# STM32G473RET6_PINOUT.net
KiCad netlist of a schematic drawn in Altium Designer
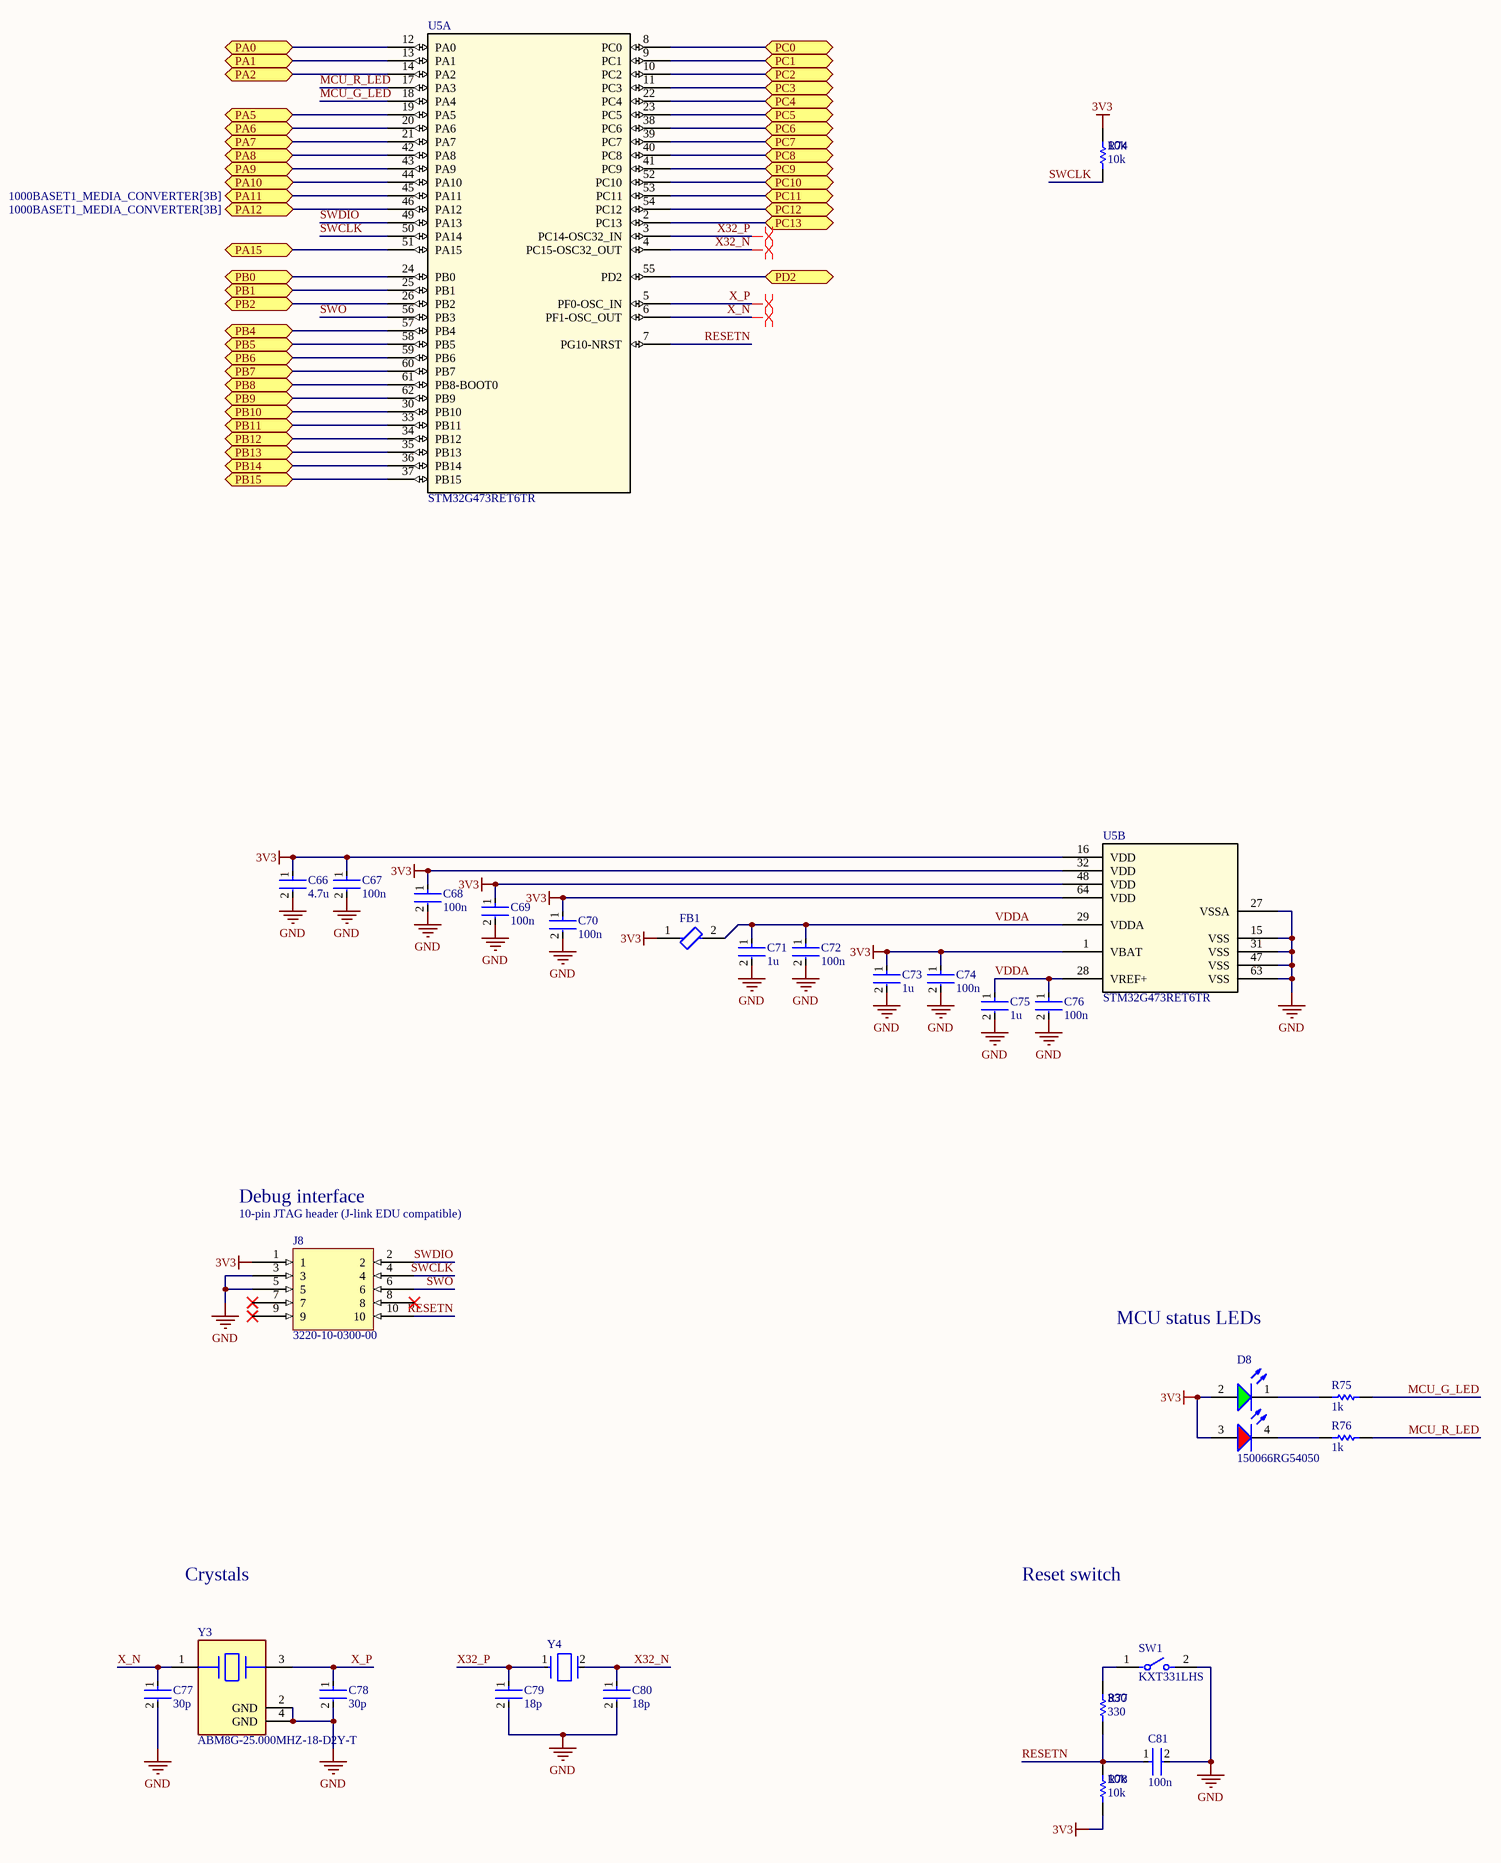
[diagram p0: STM32G473RET6_PINOUT.SchDoc]

(export (version "E")
  (design (tool "Eeschema 10.0.6"))
  (components
    (comp (ref "C66")
      (value "4.7u")
      (footprint "FP-0402-L_1_0_0_05-W_0_5-IPC_A")
      (description "LARGE PADS, 0402 CAP, CHANGE COMMENT TO MATCH REAL P/N")
      (libsource (lib "Space Concordia") (part "b4654b650e69147ec39a6b967a45e02"))
    )
    (comp (ref "C67")
      (value "100n")
      (footprint "FP-0402-L_1_0_0_05-W_0_5-IPC_A")
      (description "LARGE PADS, 0402 CAP, CHANGE COMMENT TO MATCH REAL P/N")
      (libsource (lib "Space Concordia") (part "b4654b650e69147ec39a6b967a45e02"))
    )
    (comp (ref "C68")
      (value "100n")
      (footprint "FP-0402-L_1_0_0_05-W_0_5-IPC_A")
      (description "LARGE PADS, 0402 CAP, CHANGE COMMENT TO MATCH REAL P/N")
      (libsource (lib "Space Concordia") (part "b4654b650e69147ec39a6b967a45e02"))
    )
    (comp (ref "C69")
      (value "100n")
      (footprint "FP-0402-L_1_0_0_05-W_0_5-IPC_A")
      (description "LARGE PADS, 0402 CAP, CHANGE COMMENT TO MATCH REAL P/N")
      (libsource (lib "Space Concordia") (part "b4654b650e69147ec39a6b967a45e02"))
    )
    (comp (ref "C70")
      (value "100n")
      (footprint "FP-0402-L_1_0_0_05-W_0_5-IPC_A")
      (description "LARGE PADS, 0402 CAP, CHANGE COMMENT TO MATCH REAL P/N")
      (libsource (lib "Space Concordia") (part "b4654b650e69147ec39a6b967a45e02"))
    )
    (comp (ref "C71")
      (value "1u")
      (footprint "FP-0402-L_1_0_0_05-W_0_5-IPC_A")
      (description "LARGE PADS, 0402 CAP, CHANGE COMMENT TO MATCH REAL P/N")
      (libsource (lib "Space Concordia") (part "b4654b650e69147ec39a6b967a45e02"))
    )
    (comp (ref "C72")
      (value "100n")
      (footprint "FP-0402-L_1_0_0_05-W_0_5-IPC_A")
      (description "LARGE PADS, 0402 CAP, CHANGE COMMENT TO MATCH REAL P/N")
      (libsource (lib "Space Concordia") (part "b4654b650e69147ec39a6b967a45e02"))
    )
    (comp (ref "C73")
      (value "1u")
      (footprint "FP-0402-L_1_0_0_05-W_0_5-IPC_A")
      (description "LARGE PADS, 0402 CAP, CHANGE COMMENT TO MATCH REAL P/N")
      (libsource (lib "Space Concordia") (part "b4654b650e69147ec39a6b967a45e02"))
    )
    (comp (ref "C74")
      (value "100n")
      (footprint "FP-0402-L_1_0_0_05-W_0_5-IPC_A")
      (description "LARGE PADS, 0402 CAP, CHANGE COMMENT TO MATCH REAL P/N")
      (libsource (lib "Space Concordia") (part "b4654b650e69147ec39a6b967a45e02"))
    )
    (comp (ref "C75")
      (value "1u")
      (footprint "FP-0402-L_1_0_0_05-W_0_5-IPC_A")
      (description "LARGE PADS, 0402 CAP, CHANGE COMMENT TO MATCH REAL P/N")
      (libsource (lib "Space Concordia") (part "b4654b650e69147ec39a6b967a45e02"))
    )
    (comp (ref "C76")
      (value "100n")
      (footprint "FP-0402-L_1_0_0_05-W_0_5-IPC_A")
      (description "LARGE PADS, 0402 CAP, CHANGE COMMENT TO MATCH REAL P/N")
      (libsource (lib "Space Concordia") (part "b4654b650e69147ec39a6b967a45e02"))
    )
    (comp (ref "C77")
      (value "30p")
      (footprint "FP-0402-L_1_0_0_05-W_0_5-IPC_A")
      (description "LARGE PADS, 0402 CAP, CHANGE COMMENT TO MATCH REAL P/N")
      (libsource (lib "Space Concordia") (part "b4654b650e69147ec39a6b967a45e02"))
    )
    (comp (ref "C78")
      (value "30p")
      (footprint "FP-0402-L_1_0_0_05-W_0_5-IPC_A")
      (description "LARGE PADS, 0402 CAP, CHANGE COMMENT TO MATCH REAL P/N")
      (libsource (lib "Space Concordia") (part "b4654b650e69147ec39a6b967a45e02"))
    )
    (comp (ref "C79")
      (value "18p")
      (footprint "FP-0402-L_1_0_0_05-W_0_5-IPC_A")
      (description "LARGE PADS, 0402 CAP, CHANGE COMMENT TO MATCH REAL P/N")
      (libsource (lib "Space Concordia") (part "b4654b650e69147ec39a6b967a45e02"))
    )
    (comp (ref "C80")
      (value "18p")
      (footprint "FP-0402-L_1_0_0_05-W_0_5-IPC_A")
      (description "LARGE PADS, 0402 CAP, CHANGE COMMENT TO MATCH REAL P/N")
      (libsource (lib "Space Concordia") (part "b4654b650e69147ec39a6b967a45e02"))
    )
    (comp (ref "C81")
      (value "100n")
      (footprint "FP-0402-L_1_0_0_05-W_0_5-IPC_A")
      (description "LARGE PADS, 0402 CAP, CHANGE COMMENT TO MATCH REAL P/N")
      (libsource (lib "Space Concordia") (part "b4654b650e69147ec39a6b967a45e02"))
    )
    (comp (ref "D8")
      (value "150066RG54050")
      (footprint "WL-SBCD_0606")
      (description "Led, Red/Grn, 180Mcd/230Mcd, 624Nm/525Nm Rohs Compliant: Yes")
      (fields (field (name "SOURCE") "rgled.SchLib"))
      (libsource (lib "Space Concordia") (part "CMP-004-00034-2"))
    )
    (comp (ref "FB1")
      (value "BLM15PX601SN1D")
      (footprint "FP-BLM15-0_05-MFG")
      (description "Chip Ferrite Bead, 0402, 600Ω @ 100MHz, 0.23Ω, 25%, 900mA")
      (fields (field (name "TOLERANCE") "25%"))
      (libsource (lib "Altium Content Vault") (part "5f30dd21d616792df468990f7003faa"))
    )
    (comp (ref "J8")
      (value "3220-10-0300-00")
      (footprint "3220-10-0300-00-Footprint-1")
      (description "CONN HEADER SMD 10POS 1.27MM")
      (libsource (lib "Space Concordia") (part "3220-10-0300-00"))
    )
    (comp (ref "R74")
      (value "10k")
      (footprint "R0603B")
      (description "Resistor")
      (fields (field (name "ALTIUM_VALUE") "10k"))
      (libsource (lib "Space Concordia") (part "Resistor"))
    )
    (comp (ref "R75")
      (value "1k")
      (footprint "R0603B")
      (description "Resistor")
      (libsource (lib "Space Concordia") (part "Resistor"))
    )
    (comp (ref "R76")
      (value "1k")
      (footprint "R0603B")
      (description "Resistor")
      (libsource (lib "Space Concordia") (part "Resistor"))
    )
    (comp (ref "R77")
      (value "330")
      (footprint "R0603B")
      (description "Resistor")
      (fields (field (name "ALTIUM_VALUE") "330"))
      (libsource (lib "Space Concordia") (part "Resistor"))
    )
    (comp (ref "R78")
      (value "10k")
      (footprint "R0603B")
      (description "Resistor")
      (fields (field (name "ALTIUM_VALUE") "10k"))
      (libsource (lib "Space Concordia") (part "Resistor"))
    )
    (comp (ref "SW1")
      (value "KXT331LHS")
      (footprint "FP-KXT331LHS-MFG")
      (description "SWITCH TACTILE SPST-NO 0.02A 15V")
      (libsource (lib "Altium Content Vault") (part "bb27bde45df87f1f469753f287ef5ae"))
    )
    (comp (ref "U5")
      (value "STM32G473RET6TR")
      (footprint "STM32G473RET6TR-Footprint-1")
      (description "MCU 32-Bit STM32 ARM Cortex-M4 RISC 512KB Flash 1.71V to 3.6V 64-Pin LQFP T/R")
      (libsource (lib "Space Concordia") (part "STM32G473RET6TR"))
    )
    (comp (ref "Y3")
      (value "ABM8G-25.000MHZ-18-D2Y-T")
      (footprint "FP-ABM8G-MFG")
      (description "Crystal 25MHz ±20ppm (Tol) ±30ppm (Stability) 18pF FUND 60Ω 4-Pin SMD T/R")
      (fields (field (name "TOLERANCE") "20ppm"))
      (libsource (lib "Altium Content Vault") (part "48e526d86b7f2615d98721063c72f49"))
    )
    (comp (ref "Y4")
      (value "ECS-.327-12.5-1210-TR")
      (footprint "FP-ECX-1210-MFG")
      (description "CRYSTAL 32.7680KHZ 12.5PF SMD")
      (fields
        (field (name "OCTOPART") "https://octopart.com/ecs-.327-12.5-1210-tr-ecs+international-81221340")
        (field (name "TOLERANCE") "20ppm")
      )
      (libsource (lib "Altium Content Vault") (part "99724985039315a44fd0d1401b84e49"))
    )
  )
  (nets
    (net (code "1") (name "/MCU_G_LED") (class "Default")
      (node (ref "R75") (pin "1") (pinfunction "1_1") (pintype "passive"))
      (node (ref "U5") (pin "18") (pinfunction "PA4_18") (pintype "bidirectional"))
    )
    (net (code "2") (name "/MCU_R_LED") (class "Default")
      (node (ref "R76") (pin "1") (pinfunction "1_1") (pintype "passive"))
      (node (ref "U5") (pin "17") (pinfunction "PA3_17") (pintype "bidirectional"))
    )
    (net (code "3") (name "/PA0") (class "Default")
      (node (ref "U5") (pin "12") (pinfunction "PA0_12") (pintype "bidirectional"))
    )
    (net (code "4") (name "/PA1") (class "Default")
      (node (ref "U5") (pin "13") (pinfunction "PA1_13") (pintype "bidirectional"))
    )
    (net (code "5") (name "/PA2") (class "Default")
      (node (ref "U5") (pin "14") (pinfunction "PA2_14") (pintype "bidirectional"))
    )
    (net (code "6") (name "/PA5") (class "Default")
      (node (ref "U5") (pin "19") (pinfunction "PA5_19") (pintype "bidirectional"))
    )
    (net (code "7") (name "/PA6") (class "Default")
      (node (ref "U5") (pin "20") (pinfunction "PA6_20") (pintype "bidirectional"))
    )
    (net (code "8") (name "/PA7") (class "Default")
      (node (ref "U5") (pin "21") (pinfunction "PA7_21") (pintype "bidirectional"))
    )
    (net (code "9") (name "/PA8") (class "Default")
      (node (ref "U5") (pin "42") (pinfunction "PA8_42") (pintype "bidirectional"))
    )
    (net (code "10") (name "/PA9") (class "Default")
      (node (ref "U5") (pin "43") (pinfunction "PA9_43") (pintype "bidirectional"))
    )
    (net (code "11") (name "/PA10") (class "Default")
      (node (ref "U5") (pin "44") (pinfunction "PA10_44") (pintype "bidirectional"))
    )
    (net (code "12") (name "/PA11") (class "Default")
      (node (ref "U5") (pin "45") (pinfunction "PA11_45") (pintype "bidirectional"))
    )
    (net (code "13") (name "/PA12") (class "Default")
      (node (ref "U5") (pin "46") (pinfunction "PA12_46") (pintype "bidirectional"))
    )
    (net (code "14") (name "/PA15") (class "Default")
      (node (ref "U5") (pin "51") (pinfunction "PA15_51") (pintype "bidirectional"))
    )
    (net (code "15") (name "/PB0") (class "Default")
      (node (ref "U5") (pin "24") (pinfunction "PB0_24") (pintype "bidirectional"))
    )
    (net (code "16") (name "/PB1") (class "Default")
      (node (ref "U5") (pin "25") (pinfunction "PB1_25") (pintype "bidirectional"))
    )
    (net (code "17") (name "/PB2") (class "Default")
      (node (ref "U5") (pin "26") (pinfunction "PB2_26") (pintype "bidirectional"))
    )
    (net (code "18") (name "/PB4") (class "Default")
      (node (ref "U5") (pin "57") (pinfunction "PB4_57") (pintype "bidirectional"))
    )
    (net (code "19") (name "/PB5") (class "Default")
      (node (ref "U5") (pin "58") (pinfunction "PB5_58") (pintype "bidirectional"))
    )
    (net (code "20") (name "/PB6") (class "Default")
      (node (ref "U5") (pin "59") (pinfunction "PB6_59") (pintype "bidirectional"))
    )
    (net (code "21") (name "/PB7") (class "Default")
      (node (ref "U5") (pin "60") (pinfunction "PB7_60") (pintype "bidirectional"))
    )
    (net (code "22") (name "/PB8") (class "Default")
      (node (ref "U5") (pin "61") (pinfunction "PB8-BOOT0_61") (pintype "bidirectional"))
    )
    (net (code "23") (name "/PB9") (class "Default")
      (node (ref "U5") (pin "62") (pinfunction "PB9_62") (pintype "bidirectional"))
    )
    (net (code "24") (name "/PB10") (class "Default")
      (node (ref "U5") (pin "30") (pinfunction "PB10_30") (pintype "bidirectional"))
    )
    (net (code "25") (name "/PB11") (class "Default")
      (node (ref "U5") (pin "33") (pinfunction "PB11_33") (pintype "bidirectional"))
    )
    (net (code "26") (name "/PB12") (class "Default")
      (node (ref "U5") (pin "34") (pinfunction "PB12_34") (pintype "bidirectional"))
    )
    (net (code "27") (name "/PB13") (class "Default")
      (node (ref "U5") (pin "35") (pinfunction "PB13_35") (pintype "bidirectional"))
    )
    (net (code "28") (name "/PB14") (class "Default")
      (node (ref "U5") (pin "36") (pinfunction "PB14_36") (pintype "bidirectional"))
    )
    (net (code "29") (name "/PB15") (class "Default")
      (node (ref "U5") (pin "37") (pinfunction "PB15_37") (pintype "bidirectional"))
    )
    (net (code "30") (name "/PC0") (class "Default")
      (node (ref "U5") (pin "8") (pinfunction "PC0_8") (pintype "bidirectional"))
    )
    (net (code "31") (name "/PC1") (class "Default")
      (node (ref "U5") (pin "9") (pinfunction "PC1_9") (pintype "bidirectional"))
    )
    (net (code "32") (name "/PC2") (class "Default")
      (node (ref "U5") (pin "10") (pinfunction "PC2_10") (pintype "bidirectional"))
    )
    (net (code "33") (name "/PC3") (class "Default")
      (node (ref "U5") (pin "11") (pinfunction "PC3_11") (pintype "bidirectional"))
    )
    (net (code "34") (name "/PC4") (class "Default")
      (node (ref "U5") (pin "22") (pinfunction "PC4_22") (pintype "bidirectional"))
    )
    (net (code "35") (name "/PC5") (class "Default")
      (node (ref "U5") (pin "23") (pinfunction "PC5_23") (pintype "bidirectional"))
    )
    (net (code "36") (name "/PC6") (class "Default")
      (node (ref "U5") (pin "38") (pinfunction "PC6_38") (pintype "bidirectional"))
    )
    (net (code "37") (name "/PC7") (class "Default")
      (node (ref "U5") (pin "39") (pinfunction "PC7_39") (pintype "bidirectional"))
    )
    (net (code "38") (name "/PC8") (class "Default")
      (node (ref "U5") (pin "40") (pinfunction "PC8_40") (pintype "bidirectional"))
    )
    (net (code "39") (name "/PC9") (class "Default")
      (node (ref "U5") (pin "41") (pinfunction "PC9_41") (pintype "bidirectional"))
    )
    (net (code "40") (name "/PC10") (class "Default")
      (node (ref "U5") (pin "52") (pinfunction "PC10_52") (pintype "bidirectional"))
    )
    (net (code "41") (name "/PC11") (class "Default")
      (node (ref "U5") (pin "53") (pinfunction "PC11_53") (pintype "bidirectional"))
    )
    (net (code "42") (name "/PC12") (class "Default")
      (node (ref "U5") (pin "54") (pinfunction "PC12_54") (pintype "bidirectional"))
    )
    (net (code "43") (name "/PC13") (class "Default")
      (node (ref "U5") (pin "2") (pinfunction "PC13_2") (pintype "bidirectional"))
    )
    (net (code "44") (name "/PD2") (class "Default")
      (node (ref "U5") (pin "55") (pinfunction "PD2_55") (pintype "bidirectional"))
    )
    (net (code "45") (name "/RESETN") (class "Default")
      (node (ref "C81") (pin "1") (pinfunction "1_1") (pintype "passive"))
      (node (ref "J8") (pin "10") (pinfunction "10_10") (pintype "input"))
      (node (ref "R77") (pin "1") (pinfunction "1_1") (pintype "passive"))
      (node (ref "R78") (pin "2") (pinfunction "2_2") (pintype "passive"))
      (node (ref "U5") (pin "7") (pinfunction "PG10-NRST_7") (pintype "bidirectional"))
    )
    (net (code "46") (name "/SWCLK") (class "Default")
      (node (ref "J8") (pin "4") (pinfunction "4_4") (pintype "input"))
      (node (ref "R74") (pin "1") (pinfunction "1_1") (pintype "passive"))
      (node (ref "U5") (pin "50") (pinfunction "PA14_50") (pintype "bidirectional"))
    )
    (net (code "47") (name "/SWDIO") (class "Default")
      (node (ref "J8") (pin "2") (pinfunction "2_2") (pintype "input"))
      (node (ref "U5") (pin "49") (pinfunction "PA13_49") (pintype "bidirectional"))
    )
    (net (code "48") (name "/SWO") (class "Default")
      (node (ref "J8") (pin "6") (pinfunction "6_6") (pintype "input"))
      (node (ref "U5") (pin "56") (pinfunction "PB3_56") (pintype "bidirectional"))
    )
    (net (code "49") (name "/VDDA") (class "Default")
      (node (ref "C71") (pin "1") (pinfunction "1_1") (pintype "passive"))
      (node (ref "C72") (pin "1") (pinfunction "1_1") (pintype "passive"))
      (node (ref "C75") (pin "1") (pinfunction "1_1") (pintype "passive"))
      (node (ref "C76") (pin "1") (pinfunction "1_1") (pintype "passive"))
      (node (ref "FB1") (pin "2") (pinfunction "2_2") (pintype "passive"))
      (node (ref "U5") (pin "28") (pinfunction "VREF+_28") (pintype "power_in"))
      (node (ref "U5") (pin "29") (pinfunction "VDDA_29") (pintype "power_in"))
    )
    (net (code "50") (name "/X32_N") (class "Default")
      (node (ref "C80") (pin "1") (pinfunction "1_1") (pintype "passive"))
      (node (ref "U5") (pin "4") (pinfunction "PC15-OSC32_OUT_4") (pintype "bidirectional"))
      (node (ref "Y4") (pin "2") (pinfunction "Out/In_2") (pintype "passive"))
    )
    (net (code "51") (name "/X32_P") (class "Default")
      (node (ref "C79") (pin "1") (pinfunction "1_1") (pintype "passive"))
      (node (ref "U5") (pin "3") (pinfunction "PC14-OSC32_IN_3") (pintype "bidirectional"))
      (node (ref "Y4") (pin "1") (pinfunction "In/Out_1") (pintype "passive"))
    )
    (net (code "52") (name "/X_N") (class "Default")
      (node (ref "C77") (pin "1") (pinfunction "1_1") (pintype "passive"))
      (node (ref "U5") (pin "6") (pinfunction "PF1-OSC_OUT_6") (pintype "bidirectional"))
      (node (ref "Y3") (pin "1") (pinfunction "1_1") (pintype "passive"))
    )
    (net (code "53") (name "/X_P") (class "Default")
      (node (ref "C78") (pin "1") (pinfunction "1_1") (pintype "passive"))
      (node (ref "U5") (pin "5") (pinfunction "PF0-OSC_IN_5") (pintype "bidirectional"))
      (node (ref "Y3") (pin "3") (pinfunction "3_3") (pintype "passive"))
    )
    (net (code "54") (name "3V3") (class "Default")
      (node (ref "C66") (pin "1") (pinfunction "1_1") (pintype "passive"))
      (node (ref "C67") (pin "1") (pinfunction "1_1") (pintype "passive"))
      (node (ref "C68") (pin "1") (pinfunction "1_1") (pintype "passive"))
      (node (ref "C69") (pin "1") (pinfunction "1_1") (pintype "passive"))
      (node (ref "C70") (pin "1") (pinfunction "1_1") (pintype "passive"))
      (node (ref "C73") (pin "1") (pinfunction "1_1") (pintype "passive"))
      (node (ref "C74") (pin "1") (pinfunction "1_1") (pintype "passive"))
      (node (ref "D8") (pin "2") (pinfunction "A_2") (pintype "passive"))
      (node (ref "D8") (pin "3") (pinfunction "A_3") (pintype "passive"))
      (node (ref "FB1") (pin "1") (pinfunction "1_1") (pintype "passive"))
      (node (ref "J8") (pin "1") (pinfunction "1_1") (pintype "input"))
      (node (ref "R74") (pin "2") (pinfunction "2_2") (pintype "passive"))
      (node (ref "R78") (pin "1") (pinfunction "1_1") (pintype "passive"))
      (node (ref "U5") (pin "1") (pinfunction "VBAT_1") (pintype "power_in"))
      (node (ref "U5") (pin "16") (pinfunction "VDD_16") (pintype "power_in"))
      (node (ref "U5") (pin "32") (pinfunction "VDD_32") (pintype "power_in"))
      (node (ref "U5") (pin "48") (pinfunction "VDD_48") (pintype "power_in"))
      (node (ref "U5") (pin "64") (pinfunction "VDD_64") (pintype "power_in"))
    )
    (net (code "55") (name "GND") (class "Default")
      (node (ref "C66") (pin "2") (pinfunction "2_2") (pintype "passive"))
      (node (ref "C67") (pin "2") (pinfunction "2_2") (pintype "passive"))
      (node (ref "C68") (pin "2") (pinfunction "2_2") (pintype "passive"))
      (node (ref "C69") (pin "2") (pinfunction "2_2") (pintype "passive"))
      (node (ref "C70") (pin "2") (pinfunction "2_2") (pintype "passive"))
      (node (ref "C71") (pin "2") (pinfunction "2_2") (pintype "passive"))
      (node (ref "C72") (pin "2") (pinfunction "2_2") (pintype "passive"))
      (node (ref "C73") (pin "2") (pinfunction "2_2") (pintype "passive"))
      (node (ref "C74") (pin "2") (pinfunction "2_2") (pintype "passive"))
      (node (ref "C75") (pin "2") (pinfunction "2_2") (pintype "passive"))
      (node (ref "C76") (pin "2") (pinfunction "2_2") (pintype "passive"))
      (node (ref "C77") (pin "2") (pinfunction "2_2") (pintype "passive"))
      (node (ref "C78") (pin "2") (pinfunction "2_2") (pintype "passive"))
      (node (ref "C79") (pin "2") (pinfunction "2_2") (pintype "passive"))
      (node (ref "C80") (pin "2") (pinfunction "2_2") (pintype "passive"))
      (node (ref "C81") (pin "2") (pinfunction "2_2") (pintype "passive"))
      (node (ref "J8") (pin "3") (pinfunction "3_3") (pintype "input"))
      (node (ref "J8") (pin "5") (pinfunction "5_5") (pintype "input"))
      (node (ref "SW1") (pin "2") (pinfunction "2_2") (pintype "passive"))
      (node (ref "U5") (pin "15") (pinfunction "VSS_15") (pintype "power_in"))
      (node (ref "U5") (pin "27") (pinfunction "VSSA_27") (pintype "power_in"))
      (node (ref "U5") (pin "31") (pinfunction "VSS_31") (pintype "power_in"))
      (node (ref "U5") (pin "47") (pinfunction "VSS_47") (pintype "power_in"))
      (node (ref "U5") (pin "63") (pinfunction "VSS_63") (pintype "power_in"))
      (node (ref "Y3") (pin "2") (pinfunction "GND_2") (pintype "power_in"))
      (node (ref "Y3") (pin "4") (pinfunction "GND_4") (pintype "power_in"))
    )
    (net (code "56") (name "Net-(D8-K-Pad1)") (class "Default")
      (node (ref "D8") (pin "1") (pinfunction "K_1") (pintype "passive"))
      (node (ref "R75") (pin "2") (pinfunction "2_2") (pintype "passive"))
    )
    (net (code "57") (name "Net-(D8-K-Pad4)") (class "Default")
      (node (ref "D8") (pin "4") (pinfunction "K_4") (pintype "passive"))
      (node (ref "R76") (pin "2") (pinfunction "2_2") (pintype "passive"))
    )
    (net (code "58") (name "Net-(R77-Pad2)") (class "Default")
      (node (ref "R77") (pin "2") (pinfunction "2_2") (pintype "passive"))
      (node (ref "SW1") (pin "1") (pinfunction "1_1") (pintype "passive"))
    )
    (net (code "59") (name "unconnected-(J8-Pad7)") (class "Default")
      (node (ref "J8") (pin "7") (pinfunction "7_7") (pintype "input+no_connect"))
    )
    (net (code "60") (name "unconnected-(J8-Pad8)") (class "Default")
      (node (ref "J8") (pin "8") (pinfunction "8_8") (pintype "input+no_connect"))
    )
    (net (code "61") (name "unconnected-(J8-Pad9)") (class "Default")
      (node (ref "J8") (pin "9") (pinfunction "9_9") (pintype "input+no_connect"))
    )
  )
)
